# RatDBS-Plastic2032Battery.net
KiCad netlist of a schematic drawn in EAGLE
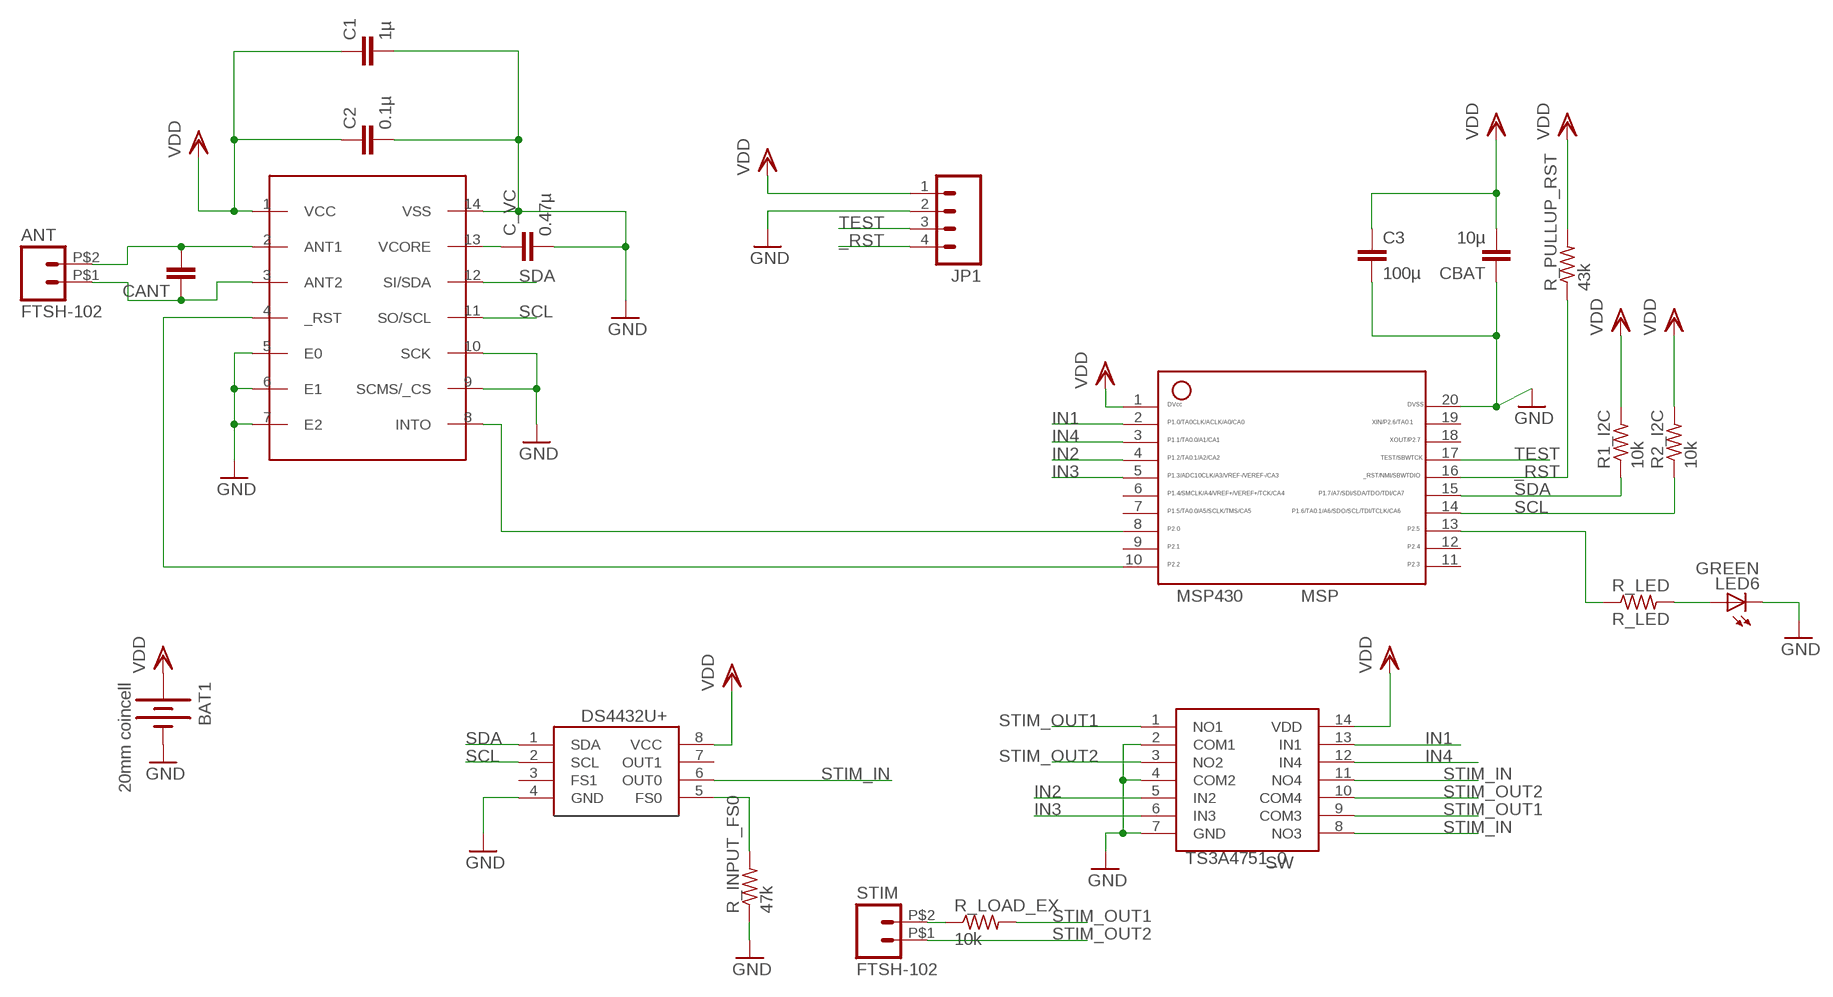
[diagram p0: schematic, sheet 1]

(export (version "E")
  (design (tool "Eeschema 10.0.6"))
  (components
    (comp (ref "ANT")
      (value "FTSH-102")
      (footprint "eagle-import:FTSH-102-DH")
      (libsource (lib "eagle-import") (part "FTSH-102"))
    )
    (comp (ref "BAT1")
      (value "20mm coincell")
      (footprint "eagle-import:BATTCOM_20MM_PLASTIC_STUDS")
      (libsource (lib "eagle-import") (part "BATTERY"))
    )
    (comp (ref "C1")
      (value "1µ")
      (footprint "eagle-import:C0603")
      (libsource (lib "eagle-import") (part "C-EUC0603"))
    )
    (comp (ref "C2")
      (value "0.1µ")
      (footprint "eagle-import:C0603")
      (libsource (lib "eagle-import") (part "C-EUC0603"))
    )
    (comp (ref "C3")
      (value "100µ")
      (footprint "eagle-import:C1206")
      (libsource (lib "eagle-import") (part "C-EUC1206"))
    )
    (comp (ref "CANT")
      (value "C-EUC0603")
      (footprint "eagle-import:C0603")
      (libsource (lib "eagle-import") (part "C-EUC0603"))
    )
    (comp (ref "CBAT")
      (value "10µ")
      (footprint "eagle-import:C0603")
      (libsource (lib "eagle-import") (part "C-EUC0603"))
    )
    (comp (ref "C_VC")
      (value "0.47µ")
      (footprint "eagle-import:C0603")
      (libsource (lib "eagle-import") (part "C-EUC0603"))
    )
    (comp (ref "DS4432U+")
      (value "DS4432U+")
      (footprint "eagle-import:8_PIN")
      (libsource (lib "eagle-import") (part "DS4432U+"))
    )
    (comp (ref "JP1")
      (value "M041.27MM")
      (footprint "eagle-import:1X04-1.27MM")
      (libsource (lib "eagle-import") (part "M041.27MM"))
    )
    (comp (ref "LED6")
      (value "GREEN")
      (footprint "eagle-import:LED-1206")
      (libsource (lib "eagle-import") (part "LED1206"))
    )
    (comp (ref "MSP430")
      (value "MSP")
      (footprint "eagle-import:20_PIN")
      (libsource (lib "eagle-import") (part "MSP430"))
    )
    (comp (ref "R1_I2C")
      (value "10k")
      (footprint "eagle-import:R0603")
      (libsource (lib "eagle-import") (part "R-US_R0603"))
    )
    (comp (ref "R2_I2C")
      (value "10k")
      (footprint "eagle-import:R0603")
      (libsource (lib "eagle-import") (part "R-US_R0603"))
    )
    (comp (ref "R_INPUT_FS0")
      (value "47k")
      (footprint "eagle-import:R0603")
      (libsource (lib "eagle-import") (part "R-US_R0603"))
    )
    (comp (ref "R_LED")
      (value "R_LED")
      (footprint "eagle-import:R0603")
      (libsource (lib "eagle-import") (part "R-US_R0603"))
    )
    (comp (ref "R_LOAD_EX")
      (value "10k")
      (footprint "eagle-import:R0603")
      (libsource (lib "eagle-import") (part "R-US_R0603"))
    )
    (comp (ref "R_PULLUP_RST")
      (value "43k")
      (footprint "eagle-import:R0603")
      (libsource (lib "eagle-import") (part "R-US_R0603"))
    )
    (comp (ref "STIM")
      (value "FTSH-102")
      (footprint "eagle-import:FTSH-102-DH")
      (libsource (lib "eagle-import") (part "FTSH-102"))
    )
    (comp (ref "TS3A4751_0")
      (value "SW")
      (footprint "eagle-import:14_PIN")
      (libsource (lib "eagle-import") (part "TS3A4751"))
    )
    (comp (ref "U$1")
      (value "RF")
      (footprint "eagle-import:PW_R-PDSO-G14")
      (libsource (lib "eagle-import") (part "RF430CL330H"))
    )
  )
  (nets
    (net (code "1") (name "/IN1") (class "Default")
      (node (ref "MSP430") (pin "2") (pinfunction "2_2") (pintype "bidirectional"))
      (node (ref "TS3A4751_0") (pin "13") (pinfunction "IN1_13") (pintype "bidirectional"))
    )
    (net (code "2") (name "/IN2") (class "Default")
      (node (ref "MSP430") (pin "4") (pinfunction "4_4") (pintype "bidirectional"))
      (node (ref "TS3A4751_0") (pin "5") (pinfunction "IN2_5") (pintype "bidirectional"))
    )
    (net (code "3") (name "/IN3") (class "Default")
      (node (ref "MSP430") (pin "5") (pinfunction "5_5") (pintype "bidirectional"))
      (node (ref "TS3A4751_0") (pin "6") (pinfunction "IN3_6") (pintype "bidirectional"))
    )
    (net (code "4") (name "/IN4") (class "Default")
      (node (ref "MSP430") (pin "3") (pinfunction "3_3") (pintype "bidirectional"))
      (node (ref "TS3A4751_0") (pin "12") (pinfunction "IN4_12") (pintype "bidirectional"))
    )
    (net (code "5") (name "/SCL") (class "Default")
      (node (ref "DS4432U+") (pin "2") (pinfunction "SCL_2") (pintype "bidirectional"))
      (node (ref "MSP430") (pin "14") (pinfunction "14_14") (pintype "bidirectional"))
      (node (ref "R2_I2C") (pin "1") (pinfunction "1_1") (pintype "passive"))
      (node (ref "U$1") (pin "11") (pinfunction "SO/SCL_11") (pintype "bidirectional"))
    )
    (net (code "6") (name "/SDA") (class "Default")
      (node (ref "DS4432U+") (pin "1") (pinfunction "SDA_1") (pintype "bidirectional"))
      (node (ref "MSP430") (pin "15") (pinfunction "15_15") (pintype "bidirectional"))
      (node (ref "R1_I2C") (pin "1") (pinfunction "1_1") (pintype "passive"))
      (node (ref "U$1") (pin "12") (pinfunction "SI/SDA_12") (pintype "bidirectional"))
    )
    (net (code "7") (name "/STIM_IN") (class "Default")
      (node (ref "DS4432U+") (pin "6") (pinfunction "OUT0_6") (pintype "bidirectional"))
      (node (ref "TS3A4751_0") (pin "11") (pinfunction "NO4_11") (pintype "bidirectional"))
      (node (ref "TS3A4751_0") (pin "8") (pinfunction "NO3_8") (pintype "bidirectional"))
    )
    (net (code "8") (name "/STIM_OUT1") (class "Default")
      (node (ref "R_LOAD_EX") (pin "2") (pinfunction "2_2") (pintype "passive"))
      (node (ref "TS3A4751_0") (pin "1") (pinfunction "NO1_1") (pintype "bidirectional"))
      (node (ref "TS3A4751_0") (pin "9") (pinfunction "COM3_9") (pintype "bidirectional"))
    )
    (net (code "9") (name "/STIM_OUT2") (class "Default")
      (node (ref "STIM") (pin "P$1") (pinfunction "1_P$1") (pintype "passive"))
      (node (ref "TS3A4751_0") (pin "10") (pinfunction "COM4_10") (pintype "bidirectional"))
      (node (ref "TS3A4751_0") (pin "3") (pinfunction "NO2_3") (pintype "bidirectional"))
    )
    (net (code "10") (name "/TEST") (class "Default")
      (node (ref "JP1") (pin "3") (pinfunction "3_3") (pintype "passive"))
      (node (ref "MSP430") (pin "17") (pinfunction "17_17") (pintype "bidirectional"))
    )
    (net (code "11") (name "/_RST") (class "Default")
      (node (ref "JP1") (pin "4") (pinfunction "4_4") (pintype "passive"))
      (node (ref "MSP430") (pin "16") (pinfunction "16_16") (pintype "bidirectional"))
      (node (ref "R_PULLUP_RST") (pin "1") (pinfunction "1_1") (pintype "passive"))
    )
    (net (code "12") (name "GND") (class "Default")
      (node (ref "BAT1") (pin "2") (pinfunction "-_2") (pintype "power_in"))
      (node (ref "C1") (pin "2") (pinfunction "2_2") (pintype "passive"))
      (node (ref "C2") (pin "2") (pinfunction "2_2") (pintype "passive"))
      (node (ref "C3") (pin "2") (pinfunction "2_2") (pintype "passive"))
      (node (ref "CBAT") (pin "1") (pinfunction "1_1") (pintype "passive"))
      (node (ref "C_VC") (pin "2") (pinfunction "2_2") (pintype "passive"))
      (node (ref "DS4432U+") (pin "4") (pinfunction "GND_4") (pintype "power_in"))
      (node (ref "JP1") (pin "2") (pinfunction "2_2") (pintype "passive"))
      (node (ref "LED6") (pin "C") (pinfunction "C_C") (pintype "passive"))
      (node (ref "MSP430") (pin "20") (pinfunction "20_20") (pintype "bidirectional"))
      (node (ref "R_INPUT_FS0") (pin "1") (pinfunction "1_1") (pintype "passive"))
      (node (ref "TS3A4751_0") (pin "2") (pinfunction "COM1_2") (pintype "bidirectional"))
      (node (ref "TS3A4751_0") (pin "4") (pinfunction "COM2_4") (pintype "bidirectional"))
      (node (ref "TS3A4751_0") (pin "7") (pinfunction "GND_7") (pintype "bidirectional"))
      (node (ref "U$1") (pin "10") (pinfunction "SCK_10") (pintype "bidirectional"))
      (node (ref "U$1") (pin "14") (pinfunction "VSS_14") (pintype "power_in"))
      (node (ref "U$1") (pin "5") (pinfunction "E0_5") (pintype "bidirectional"))
      (node (ref "U$1") (pin "6") (pinfunction "E1_6") (pintype "bidirectional"))
      (node (ref "U$1") (pin "7") (pinfunction "E2_7") (pintype "bidirectional"))
      (node (ref "U$1") (pin "9") (pinfunction "SCMS/_CS_9") (pintype "bidirectional"))
    )
    (net (code "13") (name "Net-(ANT-1)") (class "Default")
      (node (ref "ANT") (pin "P$1") (pinfunction "1_P$1") (pintype "passive"))
      (node (ref "CANT") (pin "1") (pinfunction "1_1") (pintype "passive"))
      (node (ref "U$1") (pin "3") (pinfunction "ANT2_3") (pintype "bidirectional"))
    )
    (net (code "14") (name "Net-(ANT-2)") (class "Default")
      (node (ref "ANT") (pin "P$2") (pinfunction "2_P$2") (pintype "passive"))
      (node (ref "CANT") (pin "2") (pinfunction "2_2") (pintype "passive"))
      (node (ref "U$1") (pin "2") (pinfunction "ANT1_2") (pintype "bidirectional"))
    )
    (net (code "15") (name "Net-(DS4432U+-FS0)") (class "Default")
      (node (ref "DS4432U+") (pin "5") (pinfunction "FS0_5") (pintype "bidirectional"))
      (node (ref "R_INPUT_FS0") (pin "2") (pinfunction "2_2") (pintype "passive"))
    )
    (net (code "16") (name "Net-(LED6-PadA)") (class "Default")
      (node (ref "LED6") (pin "A") (pinfunction "A_A") (pintype "passive"))
      (node (ref "R_LED") (pin "2") (pinfunction "2_2") (pintype "passive"))
    )
    (net (code "17") (name "Net-(MSP430-Pad13)") (class "Default")
      (node (ref "MSP430") (pin "13") (pinfunction "13_13") (pintype "bidirectional"))
      (node (ref "R_LED") (pin "1") (pinfunction "1_1") (pintype "passive"))
    )
    (net (code "18") (name "Net-(STIM-2)") (class "Default")
      (node (ref "R_LOAD_EX") (pin "1") (pinfunction "1_1") (pintype "passive"))
      (node (ref "STIM") (pin "P$2") (pinfunction "2_P$2") (pintype "passive"))
    )
    (net (code "19") (name "Net-(U$1-INTO)") (class "Default")
      (node (ref "MSP430") (pin "8") (pinfunction "8_8") (pintype "bidirectional"))
      (node (ref "U$1") (pin "8") (pinfunction "INTO_8") (pintype "bidirectional"))
    )
    (net (code "20") (name "Net-(U$1-VCORE)") (class "Default")
      (node (ref "C_VC") (pin "1") (pinfunction "1_1") (pintype "passive"))
      (node (ref "U$1") (pin "13") (pinfunction "VCORE_13") (pintype "bidirectional"))
    )
    (net (code "21") (name "Net-(U$1-_RST)") (class "Default")
      (node (ref "MSP430") (pin "10") (pinfunction "10_10") (pintype "bidirectional"))
      (node (ref "U$1") (pin "4") (pinfunction "_RST_4") (pintype "bidirectional"))
    )
    (net (code "22") (name "VDD") (class "Default")
      (node (ref "BAT1") (pin "1") (pinfunction "+_1") (pintype "power_in"))
      (node (ref "C1") (pin "1") (pinfunction "1_1") (pintype "passive"))
      (node (ref "C2") (pin "1") (pinfunction "1_1") (pintype "passive"))
      (node (ref "C3") (pin "1") (pinfunction "1_1") (pintype "passive"))
      (node (ref "CBAT") (pin "2") (pinfunction "2_2") (pintype "passive"))
      (node (ref "DS4432U+") (pin "8") (pinfunction "VCC_8") (pintype "power_in"))
      (node (ref "JP1") (pin "1") (pinfunction "1_1") (pintype "passive"))
      (node (ref "MSP430") (pin "1") (pinfunction "1_1") (pintype "bidirectional"))
      (node (ref "R1_I2C") (pin "2") (pinfunction "2_2") (pintype "passive"))
      (node (ref "R2_I2C") (pin "2") (pinfunction "2_2") (pintype "passive"))
      (node (ref "R_PULLUP_RST") (pin "2") (pinfunction "2_2") (pintype "passive"))
      (node (ref "TS3A4751_0") (pin "14") (pinfunction "VDD_14") (pintype "bidirectional"))
      (node (ref "U$1") (pin "1") (pinfunction "VCC_1") (pintype "power_in"))
    )
    (net (code "23") (name "unconnected-(DS4432U+-FS1-Pad3)") (class "Default")
      (node (ref "DS4432U+") (pin "3") (pinfunction "FS1_3") (pintype "bidirectional"))
    )
    (net (code "24") (name "unconnected-(DS4432U+-OUT1-Pad7)") (class "Default")
      (node (ref "DS4432U+") (pin "7") (pinfunction "OUT1_7") (pintype "bidirectional"))
    )
    (net (code "25") (name "unconnected-(MSP430-Pad6)") (class "Default")
      (node (ref "MSP430") (pin "6") (pinfunction "6_6") (pintype "bidirectional"))
    )
    (net (code "26") (name "unconnected-(MSP430-Pad7)") (class "Default")
      (node (ref "MSP430") (pin "7") (pinfunction "7_7") (pintype "bidirectional"))
    )
    (net (code "27") (name "unconnected-(MSP430-Pad9)") (class "Default")
      (node (ref "MSP430") (pin "9") (pinfunction "9_9") (pintype "bidirectional"))
    )
    (net (code "28") (name "unconnected-(MSP430-Pad11)") (class "Default")
      (node (ref "MSP430") (pin "11") (pinfunction "11_11") (pintype "bidirectional"))
    )
    (net (code "29") (name "unconnected-(MSP430-Pad12)") (class "Default")
      (node (ref "MSP430") (pin "12") (pinfunction "12_12") (pintype "bidirectional"))
    )
    (net (code "30") (name "unconnected-(MSP430-Pad18)") (class "Default")
      (node (ref "MSP430") (pin "18") (pinfunction "18_18") (pintype "bidirectional"))
    )
    (net (code "31") (name "unconnected-(MSP430-Pad19)") (class "Default")
      (node (ref "MSP430") (pin "19") (pinfunction "19_19") (pintype "bidirectional"))
    )
  )
)
